# ArmazConnect_-_Rev_B3.net
KiCad netlist of a schematic drawn in EAGLE
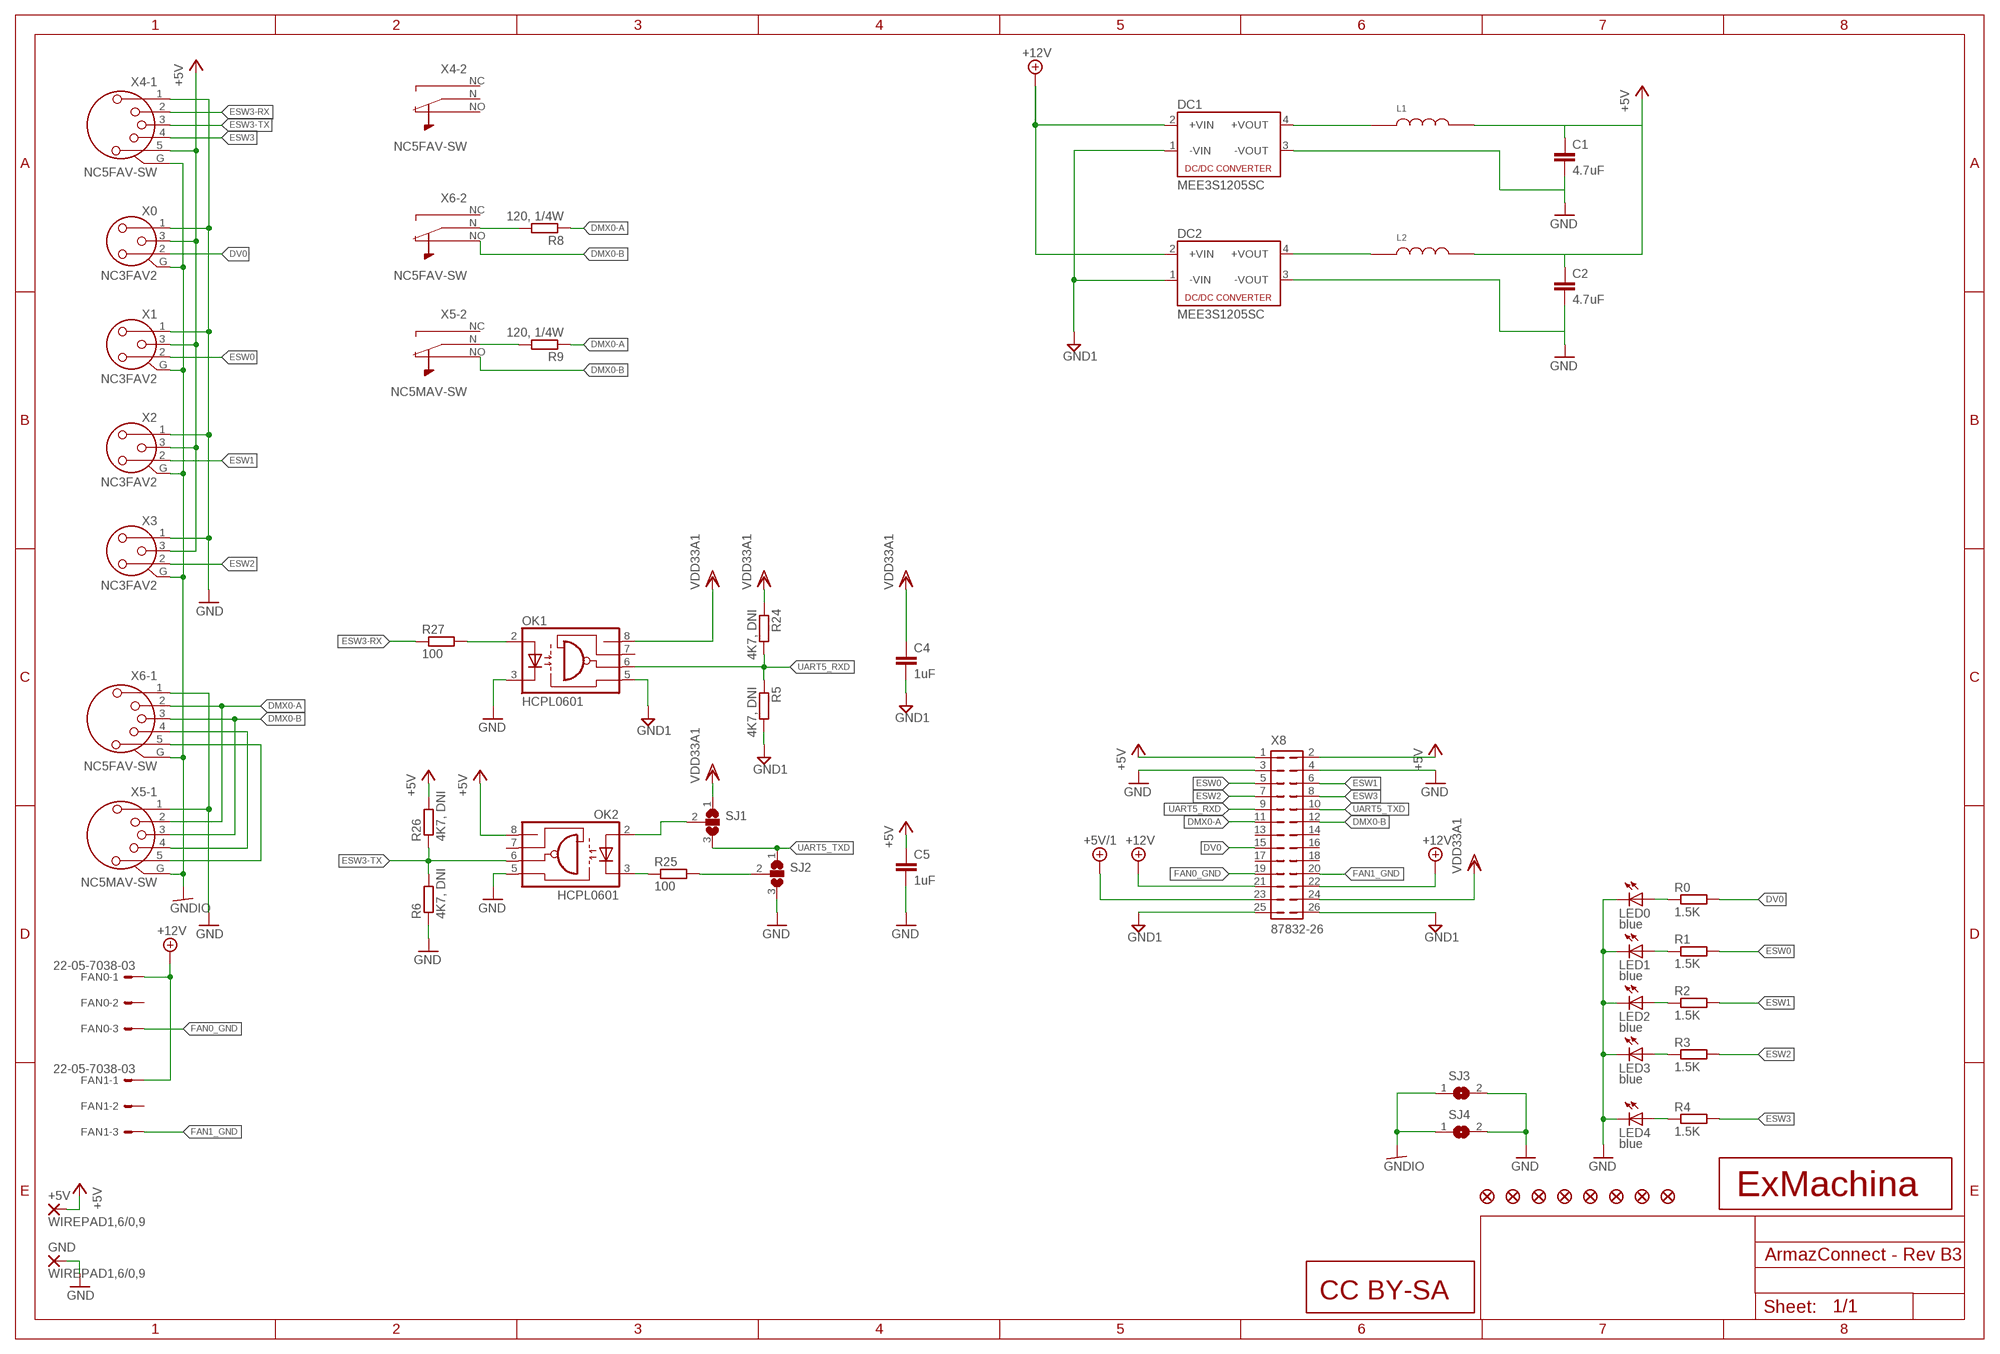
[diagram p0: schematic, sheet 1]

(export (version "E")
  (design (tool "Eeschema 10.0.6"))
  (components
    (comp (ref "+5V")
      (value "WIREPAD1,6/0,9")
      (footprint "eagle-import:1,6_0,9")
      (libsource (lib "eagle-import") (part "WIREPAD1,6/0,9"))
    )
    (comp (ref "C1")
      (value "4.7uF")
      (footprint "eagle-import:C0603")
      (fields (field (name "MF") "MULTICOMP") (field (name "MPN") "MC0603X475K6R3CT"))
      (libsource (lib "eagle-import") (part "C-EUC0603"))
    )
    (comp (ref "C2")
      (value "4.7uF")
      (footprint "eagle-import:C0603")
      (fields (field (name "MF") "MULTICOMP") (field (name "MPN") "MC0603X475K6R3CT"))
      (libsource (lib "eagle-import") (part "C-EUC0603"))
    )
    (comp (ref "C4")
      (value "1uF")
      (footprint "eagle-import:C0805")
      (fields (field (name "MF") "MULTICOMP") (field (name "MPN") "MC0805F105Z500CT"))
      (libsource (lib "eagle-import") (part "C-EUC0805"))
    )
    (comp (ref "C5")
      (value "1uF")
      (footprint "eagle-import:C0805")
      (fields (field (name "MF") "MULTICOMP") (field (name "MPN") "MC0805F105Z500CT"))
      (libsource (lib "eagle-import") (part "C-EUC0805"))
    )
    (comp (ref "DC1")
      (value "MEE3S1205SC")
      (footprint "eagle-import:MEE3")
      (fields (field (name "MF") "MURATA POWER SOLUTIONS"))
      (libsource (lib "eagle-import") (part "MEE3S1205SC"))
    )
    (comp (ref "DC2")
      (value "MEE3S1205SC")
      (footprint "eagle-import:MEE3")
      (fields (field (name "MF") "MURATA POWER SOLUTIONS"))
      (libsource (lib "eagle-import") (part "MEE3S1205SC"))
    )
    (comp (ref "FAN0")
      (value "22-05-7038-03")
      (footprint "eagle-import:7395-03")
      (fields
        (field (name "MF") "MOLEX")
        (field (name "MPN") "22-05-7038")
        (field (name "OC_FARNELL") "9731610")
      )
      (libsource (lib "eagle-import") (part "22-?-0305-7038"))
    )
    (comp (ref "FAN1")
      (value "22-05-7038-03")
      (footprint "eagle-import:7395-03")
      (fields
        (field (name "MF") "MOLEX")
        (field (name "MPN") "22-05-7038")
        (field (name "OC_FARNELL") "9731610")
      )
      (libsource (lib "eagle-import") (part "22-?-0305-7038"))
    )
    (comp (ref "FI1")
      (value "FIDUCIAL1X2")
      (footprint "eagle-import:FIDUCIAL-1X2")
      (libsource (lib "eagle-import") (part "FIDUCIAL1X2"))
    )
    (comp (ref "FI2")
      (value "FIDUCIAL1X2")
      (footprint "eagle-import:FIDUCIAL-1X2")
      (libsource (lib "eagle-import") (part "FIDUCIAL1X2"))
    )
    (comp (ref "FI3")
      (value "FIDUCIAL1X2")
      (footprint "eagle-import:FIDUCIAL-1X2")
      (libsource (lib "eagle-import") (part "FIDUCIAL1X2"))
    )
    (comp (ref "FI4")
      (value "FIDUCIAL1X2")
      (footprint "eagle-import:FIDUCIAL-1X2")
      (libsource (lib "eagle-import") (part "FIDUCIAL1X2"))
    )
    (comp (ref "FI5")
      (value "FIDUCIAL1X2")
      (footprint "eagle-import:FIDUCIAL-1X2")
      (libsource (lib "eagle-import") (part "FIDUCIAL1X2"))
    )
    (comp (ref "FI6")
      (value "FIDUCIAL1X2")
      (footprint "eagle-import:FIDUCIAL-1X2")
      (libsource (lib "eagle-import") (part "FIDUCIAL1X2"))
    )
    (comp (ref "FI7")
      (value "FIDUCIAL1X2")
      (footprint "eagle-import:FIDUCIAL-1X2")
      (libsource (lib "eagle-import") (part "FIDUCIAL1X2"))
    )
    (comp (ref "FI8")
      (value "FIDUCIAL1X2")
      (footprint "eagle-import:FIDUCIAL-1X2")
      (libsource (lib "eagle-import") (part "FIDUCIAL1X2"))
    )
    (comp (ref "GND")
      (value "WIREPAD1,6/0,9")
      (footprint "eagle-import:1,6_0,9")
      (libsource (lib "eagle-import") (part "WIREPAD1,6/0,9"))
    )
    (comp (ref "L1")
      (value "84103C")
      (footprint "eagle-import:8200")
      (fields (field (name "MF") "WURTH ELEKTRONIK") (field (name "MPN") "744045100"))
      (libsource (lib "eagle-import") (part "84103C"))
    )
    (comp (ref "L2")
      (value "84103C")
      (footprint "eagle-import:8200")
      (fields (field (name "MF") "WURTH ELEKTRONIK") (field (name "MPN") "744045100"))
      (libsource (lib "eagle-import") (part "84103C"))
    )
    (comp (ref "LED0")
      (value "blue")
      (footprint "eagle-import:CHIP-LED0603")
      (fields (field (name "MF") "MULTICOMP") (field (name "MPN") "OVS-0603"))
      (libsource (lib "eagle-import") (part "LEDCHIP-LED0603"))
    )
    (comp (ref "LED1")
      (value "blue")
      (footprint "eagle-import:CHIP-LED0603")
      (fields (field (name "MF") "MULTICOMP") (field (name "MPN") "OVS-0603"))
      (libsource (lib "eagle-import") (part "LEDCHIP-LED0603"))
    )
    (comp (ref "LED2")
      (value "blue")
      (footprint "eagle-import:CHIP-LED0603")
      (fields (field (name "MF") "MULTICOMP") (field (name "MPN") "OVS-0603"))
      (libsource (lib "eagle-import") (part "LEDCHIP-LED0603"))
    )
    (comp (ref "LED3")
      (value "blue")
      (footprint "eagle-import:CHIP-LED0603")
      (fields (field (name "MF") "MULTICOMP") (field (name "MPN") "OVS-0603"))
      (libsource (lib "eagle-import") (part "LEDCHIP-LED0603"))
    )
    (comp (ref "LED4")
      (value "blue")
      (footprint "eagle-import:CHIP-LED0603")
      (fields (field (name "MF") "MULTICOMP") (field (name "MPN") "OVS-0603"))
      (libsource (lib "eagle-import") (part "LEDCHIP-LED0603"))
    )
    (comp (ref "OK1")
      (value "HCPL0601")
      (footprint "eagle-import:SOIC08")
      (fields
        (field (name "MF") "AGILENT TECHNOLOGIES")
        (field (name "MPN") "HCPL-0601-000E")
        (field (name "MF_1") "AVAGO TECHNOLOGIES")
      )
      (libsource (lib "eagle-import") (part "HCPL0601"))
    )
    (comp (ref "OK2")
      (value "HCPL0601")
      (footprint "eagle-import:SOIC08")
      (fields
        (field (name "MF") "AGILENT TECHNOLOGIES")
        (field (name "MPN") "HCPL-0601-000E")
        (field (name "MF_1") "AVAGO TECHNOLOGIES")
      )
      (libsource (lib "eagle-import") (part "HCPL0601"))
    )
    (comp (ref "R0")
      (value "1.5K")
      (footprint "eagle-import:R0603")
      (fields (field (name "MF") "MULTICOMP") (field (name "MPN") "MCMR06X1501FTL"))
      (libsource (lib "eagle-import") (part "R-EU_R0603"))
    )
    (comp (ref "R1")
      (value "1.5K")
      (footprint "eagle-import:R0603")
      (fields (field (name "MF") "MULTICOMP") (field (name "MPN") "MCMR06X1501FTL"))
      (libsource (lib "eagle-import") (part "R-EU_R0603"))
    )
    (comp (ref "R2")
      (value "1.5K")
      (footprint "eagle-import:R0603")
      (fields (field (name "MF") "MULTICOMP") (field (name "MPN") "MCMR06X1501FTL"))
      (libsource (lib "eagle-import") (part "R-EU_R0603"))
    )
    (comp (ref "R3")
      (value "1.5K")
      (footprint "eagle-import:R0603")
      (fields (field (name "MF") "MULTICOMP") (field (name "MPN") "MCMR06X1501FTL"))
      (libsource (lib "eagle-import") (part "R-EU_R0603"))
    )
    (comp (ref "R4")
      (value "1.5K")
      (footprint "eagle-import:R0603")
      (fields (field (name "MF") "MULTICOMP") (field (name "MPN") "MCMR06X1501FTL"))
      (libsource (lib "eagle-import") (part "R-EU_R0603"))
    )
    (comp (ref "R5")
      (value "4K7, DNI")
      (footprint "eagle-import:R0603")
      (fields (field (name "MF") "MULTICOMP") (field (name "MPN") "MCMR04X3301FTL"))
      (libsource (lib "eagle-import") (part "R-EU_R0603"))
    )
    (comp (ref "R6")
      (value "4K7, DNI")
      (footprint "eagle-import:R0603")
      (fields (field (name "MF") "MULTICOMP") (field (name "MPN") "MCMR06X4701FTL"))
      (libsource (lib "eagle-import") (part "R-EU_R0603"))
    )
    (comp (ref "R8")
      (value "120, 1/4W")
      (footprint "eagle-import:R0603")
      (fields (field (name "MF") "MULTICOMP") (field (name "MPN") "MCMR06X1200FTL"))
      (libsource (lib "eagle-import") (part "R-EU_R0603"))
    )
    (comp (ref "R9")
      (value "120, 1/4W")
      (footprint "eagle-import:R0603")
      (fields (field (name "MF") "MULTICOMP") (field (name "MPN") "MCMR06X1200FTL"))
      (libsource (lib "eagle-import") (part "R-EU_R0603"))
    )
    (comp (ref "R24")
      (value "4K7, DNI")
      (footprint "eagle-import:R0603")
      (fields (field (name "MF") "MULTICOMP") (field (name "MPN") "MCMR04X3301FTL"))
      (libsource (lib "eagle-import") (part "R-EU_R0603"))
    )
    (comp (ref "R25")
      (value "100")
      (footprint "eagle-import:R0603")
      (fields (field (name "MF") "MULTICOMP") (field (name "MPN") "MCMR06X3300FTL"))
      (libsource (lib "eagle-import") (part "R-EU_R0603"))
    )
    (comp (ref "R26")
      (value "4K7, DNI")
      (footprint "eagle-import:R0603")
      (fields (field (name "MF") "MULTICOMP") (field (name "MPN") "MCMR06X4701FTL"))
      (libsource (lib "eagle-import") (part "R-EU_R0603"))
    )
    (comp (ref "R27")
      (value "100")
      (footprint "eagle-import:R0603")
      (fields (field (name "MF") "MULTICOMP") (field (name "MPN") "MCMR06X4701FTL"))
      (libsource (lib "eagle-import") (part "R-EU_R0603"))
    )
    (comp (ref "SJ1")
      (value "SJ2W")
      (footprint "eagle-import:SJ_2")
      (libsource (lib "eagle-import") (part "SJ2W"))
    )
    (comp (ref "SJ2")
      (value "SJ2W")
      (footprint "eagle-import:SJ_2")
      (libsource (lib "eagle-import") (part "SJ2W"))
    )
    (comp (ref "SJ3") (value "SJ") (footprint "eagle-import:SJ") (libsource (lib "eagle-import") (part "SJ")))
    (comp (ref "SJ4") (value "SJ") (footprint "eagle-import:SJ") (libsource (lib "eagle-import") (part "SJ")))
    (comp (ref "U$1")
      (value "EXMACHINA-LOGO-NAME")
      (footprint "eagle-import:EXM-LOGO-BASELINE")
      (libsource (lib "eagle-import") (part "EXMACHINA-LOGO-NAME"))
    )
    (comp (ref "U$2")
      (value "CC-BY-SA")
      (footprint "eagle-import:CC-BY-SA")
      (libsource (lib "eagle-import") (part "CC-BY-SA"))
    )
    (comp (ref "X0")
      (value "NC3FAV2")
      (footprint "eagle-import:NC3FAV2")
      (fields
        (field (name "MF") "NEUTRIK")
        (field (name "MPN") "NC3FAAV2")
        (field (name "OC_FARNELL") "1310038")
      )
      (libsource (lib "eagle-import") (part "NC3FAV2"))
    )
    (comp (ref "X1")
      (value "NC3FAV2")
      (footprint "eagle-import:NC3FAV2")
      (fields
        (field (name "MF") "NEUTRIK")
        (field (name "MPN") "NC3FAAV2")
        (field (name "OC_FARNELL") "1310038")
      )
      (libsource (lib "eagle-import") (part "NC3FAV2"))
    )
    (comp (ref "X2")
      (value "NC3FAV2")
      (footprint "eagle-import:NC3FAV2")
      (fields
        (field (name "MF") "NEUTRIK")
        (field (name "MPN") "NC3FAAV2")
        (field (name "OC_FARNELL") "1310038")
      )
      (libsource (lib "eagle-import") (part "NC3FAV2"))
    )
    (comp (ref "X3")
      (value "NC3FAV2")
      (footprint "eagle-import:NC3FAV2")
      (fields
        (field (name "MF") "NEUTRIK")
        (field (name "MPN") "NC3FAAV2")
        (field (name "OC_FARNELL") "1310038")
      )
      (libsource (lib "eagle-import") (part "NC3FAV2"))
    )
    (comp (ref "X4")
      (value "NC5FAV-SW")
      (footprint "eagle-import:NC5FAV-SW")
      (fields (field (name "MF") "NEUTRIK") (field (name "OC_FARNELL") "1310093"))
      (libsource (lib "eagle-import") (part "NC5?-SWFAV"))
    )
    (comp (ref "X5")
      (value "NC5MAV-SW")
      (footprint "eagle-import:NC5MAV-SW")
      (fields
        (field (name "MF") "NETRIK")
        (field (name "MF_1") "NEUTRIK")
        (field (name "OC_FARNELL") "1310098")
      )
      (libsource (lib "eagle-import") (part "NC5?-SWMAV"))
    )
    (comp (ref "X6")
      (value "NC5FAV-SW")
      (footprint "eagle-import:NC5FAV-SW")
      (fields (field (name "MF") "NEUTRIK") (field (name "OC_FARNELL") "1310093"))
      (libsource (lib "eagle-import") (part "NC5?-SWFAV"))
    )
    (comp (ref "X8")
      (value "87832-26")
      (footprint "eagle-import:87832-26")
      (fields
        (field (name "MF") "MOLEX")
        (field (name "MPN") "87832-2620")
        (field (name "OC_FARNELL") "2313712")
      )
      (libsource (lib "eagle-import") (part "87832-26"))
    )
  )
  (nets
    (net (code "1") (name "+5V") (class "Default")
      (node (ref "+5V") (pin "1") (pinfunction "P_1") (pintype "passive"))
      (node (ref "C1") (pin "1") (pinfunction "1_1") (pintype "passive"))
      (node (ref "C2") (pin "1") (pinfunction "1_1") (pintype "passive"))
      (node (ref "C5") (pin "1") (pinfunction "1_1") (pintype "passive"))
      (node (ref "L1") (pin "2") (pinfunction "2_2") (pintype "passive"))
      (node (ref "L2") (pin "2") (pinfunction "2_2") (pintype "passive"))
      (node (ref "OK2") (pin "8") (pinfunction "VCC_8") (pintype "passive"))
      (node (ref "R26") (pin "2") (pinfunction "2_2") (pintype "passive"))
      (node (ref "X0") (pin "3") (pinfunction "3_3") (pintype "passive"))
      (node (ref "X1") (pin "3") (pinfunction "3_3") (pintype "passive"))
      (node (ref "X2") (pin "3") (pinfunction "3_3") (pintype "passive"))
      (node (ref "X3") (pin "3") (pinfunction "3_3") (pintype "passive"))
      (node (ref "X4") (pin "5") (pinfunction "5_5") (pintype "passive"))
      (node (ref "X8") (pin "1") (pinfunction "1_1") (pintype "passive"))
      (node (ref "X8") (pin "2") (pinfunction "2_2") (pintype "passive"))
    )
    (net (code "2") (name "+5V{slash}1") (class "Default")
      (node (ref "X8") (pin "23") (pinfunction "23_23") (pintype "passive"))
    )
    (net (code "3") (name "+12V") (class "Default")
      (node (ref "DC1") (pin "2") (pinfunction "+VIN_2") (pintype "passive"))
      (node (ref "DC2") (pin "2") (pinfunction "+VIN_2") (pintype "passive"))
      (node (ref "FAN0") (pin "1") (pinfunction "S_1") (pintype "passive"))
      (node (ref "FAN1") (pin "1") (pinfunction "S_1") (pintype "passive"))
      (node (ref "X8") (pin "21") (pinfunction "21_21") (pintype "passive"))
      (node (ref "X8") (pin "22") (pinfunction "22_22") (pintype "passive"))
    )
    (net (code "4") (name "DMX0-A") (class "Default")
      (node (ref "R8") (pin "1") (pinfunction "1_1") (pintype "passive"))
      (node (ref "R9") (pin "1") (pinfunction "1_1") (pintype "passive"))
      (node (ref "X5") (pin "2") (pinfunction "2_2") (pintype "passive"))
      (node (ref "X6") (pin "2") (pinfunction "2_2") (pintype "passive"))
      (node (ref "X8") (pin "11") (pinfunction "11_11") (pintype "passive"))
    )
    (net (code "5") (name "DMX0-B") (class "Default")
      (node (ref "X5") (pin "3") (pinfunction "3_3") (pintype "passive"))
      (node (ref "X5") (pin "NO") (pinfunction "NO_NO") (pintype "passive"))
      (node (ref "X6") (pin "3") (pinfunction "3_3") (pintype "passive"))
      (node (ref "X6") (pin "NO") (pinfunction "NO_NO") (pintype "passive"))
      (node (ref "X8") (pin "12") (pinfunction "12_12") (pintype "passive"))
    )
    (net (code "6") (name "DV0") (class "Default")
      (node (ref "R0") (pin "2") (pinfunction "2_2") (pintype "passive"))
      (node (ref "X0") (pin "2") (pinfunction "2_2") (pintype "passive"))
      (node (ref "X8") (pin "15") (pinfunction "15_15") (pintype "passive"))
    )
    (net (code "7") (name "ESW0") (class "Default")
      (node (ref "R1") (pin "2") (pinfunction "2_2") (pintype "passive"))
      (node (ref "X1") (pin "2") (pinfunction "2_2") (pintype "passive"))
      (node (ref "X8") (pin "5") (pinfunction "5_5") (pintype "passive"))
    )
    (net (code "8") (name "ESW1") (class "Default")
      (node (ref "R2") (pin "2") (pinfunction "2_2") (pintype "passive"))
      (node (ref "X2") (pin "2") (pinfunction "2_2") (pintype "passive"))
      (node (ref "X8") (pin "6") (pinfunction "6_6") (pintype "passive"))
    )
    (net (code "9") (name "ESW2") (class "Default")
      (node (ref "R3") (pin "2") (pinfunction "2_2") (pintype "passive"))
      (node (ref "X3") (pin "2") (pinfunction "2_2") (pintype "passive"))
      (node (ref "X8") (pin "7") (pinfunction "7_7") (pintype "passive"))
    )
    (net (code "10") (name "ESW3") (class "Default")
      (node (ref "R4") (pin "2") (pinfunction "2_2") (pintype "passive"))
      (node (ref "X4") (pin "4") (pinfunction "4_4") (pintype "passive"))
      (node (ref "X8") (pin "8") (pinfunction "8_8") (pintype "passive"))
    )
    (net (code "11") (name "ESW3-RX") (class "Default")
      (node (ref "R27") (pin "1") (pinfunction "1_1") (pintype "passive"))
      (node (ref "X4") (pin "2") (pinfunction "2_2") (pintype "passive"))
    )
    (net (code "12") (name "ESW3-TX") (class "Default")
      (node (ref "OK2") (pin "6") (pinfunction "VO_6") (pintype "passive"))
      (node (ref "R26") (pin "1") (pinfunction "1_1") (pintype "passive"))
      (node (ref "R6") (pin "2") (pinfunction "2_2") (pintype "passive"))
      (node (ref "X4") (pin "3") (pinfunction "3_3") (pintype "passive"))
    )
    (net (code "13") (name "FAN0_GND") (class "Default")
      (node (ref "FAN0") (pin "3") (pinfunction "S_3") (pintype "passive"))
      (node (ref "X8") (pin "19") (pinfunction "19_19") (pintype "passive"))
    )
    (net (code "14") (name "FAN1_GND") (class "Default")
      (node (ref "FAN1") (pin "3") (pinfunction "S_3") (pintype "passive"))
      (node (ref "X8") (pin "20") (pinfunction "20_20") (pintype "passive"))
    )
    (net (code "15") (name "GND") (class "Default")
      (node (ref "C1") (pin "2") (pinfunction "2_2") (pintype "passive"))
      (node (ref "C2") (pin "2") (pinfunction "2_2") (pintype "passive"))
      (node (ref "C5") (pin "2") (pinfunction "2_2") (pintype "passive"))
      (node (ref "DC1") (pin "3") (pinfunction "-VOUT_3") (pintype "passive"))
      (node (ref "DC2") (pin "3") (pinfunction "-VOUT_3") (pintype "passive"))
      (node (ref "GND") (pin "1") (pinfunction "P_1") (pintype "passive"))
      (node (ref "LED0") (pin "C") (pinfunction "C_C") (pintype "passive"))
      (node (ref "LED1") (pin "C") (pinfunction "C_C") (pintype "passive"))
      (node (ref "LED2") (pin "C") (pinfunction "C_C") (pintype "passive"))
      (node (ref "LED3") (pin "C") (pinfunction "C_C") (pintype "passive"))
      (node (ref "LED4") (pin "C") (pinfunction "C_C") (pintype "passive"))
      (node (ref "OK1") (pin "3") (pinfunction "C_3") (pintype "passive"))
      (node (ref "OK2") (pin "5") (pinfunction "GND_5") (pintype "passive"))
      (node (ref "R6") (pin "1") (pinfunction "1_1") (pintype "passive"))
      (node (ref "SJ2") (pin "3") (pinfunction "3_3") (pintype "passive"))
      (node (ref "SJ3") (pin "2") (pinfunction "2_2") (pintype "passive"))
      (node (ref "SJ4") (pin "2") (pinfunction "2_2") (pintype "passive"))
      (node (ref "X0") (pin "1") (pinfunction "1_1") (pintype "passive"))
      (node (ref "X1") (pin "1") (pinfunction "1_1") (pintype "passive"))
      (node (ref "X2") (pin "1") (pinfunction "1_1") (pintype "passive"))
      (node (ref "X3") (pin "1") (pinfunction "1_1") (pintype "passive"))
      (node (ref "X4") (pin "1") (pinfunction "1_1") (pintype "passive"))
      (node (ref "X5") (pin "1") (pinfunction "1_1") (pintype "passive"))
      (node (ref "X6") (pin "1") (pinfunction "1_1") (pintype "passive"))
      (node (ref "X8") (pin "3") (pinfunction "3_3") (pintype "passive"))
      (node (ref "X8") (pin "4") (pinfunction "4_4") (pintype "passive"))
    )
    (net (code "16") (name "GND1") (class "Default")
      (node (ref "C4") (pin "2") (pinfunction "2_2") (pintype "passive"))
      (node (ref "DC1") (pin "1") (pinfunction "-VIN_1") (pintype "passive"))
      (node (ref "DC2") (pin "1") (pinfunction "-VIN_1") (pintype "passive"))
      (node (ref "OK1") (pin "5") (pinfunction "GND_5") (pintype "passive"))
      (node (ref "R5") (pin "2") (pinfunction "2_2") (pintype "passive"))
      (node (ref "X8") (pin "25") (pinfunction "25_25") (pintype "passive"))
      (node (ref "X8") (pin "26") (pinfunction "26_26") (pintype "passive"))
    )
    (net (code "17") (name "GNDIO") (class "Default")
      (node (ref "SJ3") (pin "1") (pinfunction "1_1") (pintype "passive"))
      (node (ref "SJ4") (pin "1") (pinfunction "1_1") (pintype "passive"))
      (node (ref "X0") (pin "G") (pinfunction "G_G") (pintype "passive"))
      (node (ref "X1") (pin "G") (pinfunction "G_G") (pintype "passive"))
      (node (ref "X2") (pin "G") (pinfunction "G_G") (pintype "passive"))
      (node (ref "X3") (pin "G") (pinfunction "G_G") (pintype "passive"))
      (node (ref "X4") (pin "G") (pinfunction "G_G") (pintype "passive"))
      (node (ref "X5") (pin "G") (pinfunction "G_G") (pintype "passive"))
      (node (ref "X6") (pin "G") (pinfunction "G_G") (pintype "passive"))
    )
    (net (code "18") (name "Net-(DC1-+VOUT)") (class "Default")
      (node (ref "DC1") (pin "4") (pinfunction "+VOUT_4") (pintype "passive"))
      (node (ref "L1") (pin "1") (pinfunction "1_1") (pintype "passive"))
    )
    (net (code "19") (name "Net-(DC2-+VOUT)") (class "Default")
      (node (ref "DC2") (pin "4") (pinfunction "+VOUT_4") (pintype "passive"))
      (node (ref "L2") (pin "1") (pinfunction "1_1") (pintype "passive"))
    )
    (net (code "20") (name "Net-(LED0-PadA)") (class "Default")
      (node (ref "LED0") (pin "A") (pinfunction "A_A") (pintype "passive"))
      (node (ref "R0") (pin "1") (pinfunction "1_1") (pintype "passive"))
    )
    (net (code "21") (name "Net-(LED1-PadA)") (class "Default")
      (node (ref "LED1") (pin "A") (pinfunction "A_A") (pintype "passive"))
      (node (ref "R1") (pin "1") (pinfunction "1_1") (pintype "passive"))
    )
    (net (code "22") (name "Net-(LED2-PadA)") (class "Default")
      (node (ref "LED2") (pin "A") (pinfunction "A_A") (pintype "passive"))
      (node (ref "R2") (pin "1") (pinfunction "1_1") (pintype "passive"))
    )
    (net (code "23") (name "Net-(LED3-PadA)") (class "Default")
      (node (ref "LED3") (pin "A") (pinfunction "A_A") (pintype "passive"))
      (node (ref "R3") (pin "1") (pinfunction "1_1") (pintype "passive"))
    )
    (net (code "24") (name "Net-(LED4-PadA)") (class "Default")
      (node (ref "LED4") (pin "A") (pinfunction "A_A") (pintype "passive"))
      (node (ref "R4") (pin "1") (pinfunction "1_1") (pintype "passive"))
    )
    (net (code "25") (name "Net-(OK1-A)") (class "Default")
      (node (ref "OK1") (pin "2") (pinfunction "A_2") (pintype "passive"))
      (node (ref "R27") (pin "2") (pinfunction "2_2") (pintype "passive"))
    )
    (net (code "26") (name "Net-(OK2-A)") (class "Default")
      (node (ref "OK2") (pin "2") (pinfunction "A_2") (pintype "passive"))
      (node (ref "SJ1") (pin "2") (pinfunction "2_2") (pintype "passive"))
    )
    (net (code "27") (name "Net-(OK2-C)") (class "Default")
      (node (ref "OK2") (pin "3") (pinfunction "C_3") (pintype "passive"))
      (node (ref "R25") (pin "1") (pinfunction "1_1") (pintype "passive"))
    )
    (net (code "28") (name "Net-(R8-Pad2)") (class "Default")
      (node (ref "R8") (pin "2") (pinfunction "2_2") (pintype "passive"))
      (node (ref "X6") (pin "N") (pinfunction "N_N") (pintype "passive"))
    )
    (net (code "29") (name "Net-(R9-Pad2)") (class "Default")
      (node (ref "R9") (pin "2") (pinfunction "2_2") (pintype "passive"))
      (node (ref "X5") (pin "N") (pinfunction "N_N") (pintype "passive"))
    )
    (net (code "30") (name "Net-(R25-Pad2)") (class "Default")
      (node (ref "R25") (pin "2") (pinfunction "2_2") (pintype "passive"))
      (node (ref "SJ2") (pin "2") (pinfunction "2_2") (pintype "passive"))
    )
    (net (code "31") (name "Net-(X5-Pad4)") (class "Default")
      (node (ref "X5") (pin "4") (pinfunction "4_4") (pintype "passive"))
      (node (ref "X6") (pin "4") (pinfunction "4_4") (pintype "passive"))
    )
    (net (code "32") (name "Net-(X5-Pad5)") (class "Default")
      (node (ref "X5") (pin "5") (pinfunction "5_5") (pintype "passive"))
      (node (ref "X6") (pin "5") (pinfunction "5_5") (pintype "passive"))
    )
    (net (code "33") (name "UART5_RXD") (class "Default")
      (node (ref "OK1") (pin "6") (pinfunction "VO_6") (pintype "passive"))
      (node (ref "R24") (pin "2") (pinfunction "2_2") (pintype "passive"))
      (node (ref "R5") (pin "1") (pinfunction "1_1") (pintype "passive"))
      (node (ref "X8") (pin "9") (pinfunction "9_9") (pintype "passive"))
    )
    (net (code "34") (name "UART5_TXD") (class "Default")
      (node (ref "SJ1") (pin "3") (pinfunction "3_3") (pintype "passive"))
      (node (ref "SJ2") (pin "1") (pinfunction "1_1") (pintype "passive"))
      (node (ref "X8") (pin "10") (pinfunction "10_10") (pintype "passive"))
    )
    (net (code "35") (name "VDD33A1") (class "Default")
      (node (ref "C4") (pin "1") (pinfunction "1_1") (pintype "passive"))
      (node (ref "OK1") (pin "8") (pinfunction "VCC_8") (pintype "passive"))
      (node (ref "R24") (pin "1") (pinfunction "1_1") (pintype "passive"))
      (node (ref "SJ1") (pin "1") (pinfunction "1_1") (pintype "passive"))
      (node (ref "X8") (pin "24") (pinfunction "24_24") (pintype "passive"))
    )
    (net (code "36") (name "unconnected-(FAN0B-S-Pad2)") (class "Default")
      (node (ref "FAN0") (pin "2") (pinfunction "S_2") (pintype "passive"))
    )
    (net (code "37") (name "unconnected-(FAN1B-S-Pad2)") (class "Default")
      (node (ref "FAN1") (pin "2") (pinfunction "S_2") (pintype "passive"))
    )
    (net (code "38") (name "unconnected-(OK1-VE-Pad7)") (class "Default")
      (node (ref "OK1") (pin "7") (pinfunction "VE_7") (pintype "passive"))
    )
    (net (code "39") (name "unconnected-(OK2-VE-Pad7)") (class "Default")
      (node (ref "OK2") (pin "7") (pinfunction "VE_7") (pintype "passive"))
    )
    (net (code "40") (name "unconnected-(X4-PadN)") (class "Default")
      (node (ref "X4") (pin "N") (pinfunction "N_N") (pintype "passive"))
    )
    (net (code "41") (name "unconnected-(X4-PadNC)") (class "Default")
      (node (ref "X4") (pin "NC") (pinfunction "NC_NC") (pintype "passive"))
    )
    (net (code "42") (name "unconnected-(X4-PadNO)") (class "Default")
      (node (ref "X4") (pin "NO") (pinfunction "NO_NO") (pintype "passive"))
    )
    (net (code "43") (name "unconnected-(X5-PadNC)") (class "Default")
      (node (ref "X5") (pin "NC") (pinfunction "NC_NC") (pintype "passive"))
    )
    (net (code "44") (name "unconnected-(X6-PadNC)") (class "Default")
      (node (ref "X6") (pin "NC") (pinfunction "NC_NC") (pintype "passive"))
    )
    (net (code "45") (name "unconnected-(X8-Pad13)") (class "Default")
      (node (ref "X8") (pin "13") (pinfunction "13_13") (pintype "passive"))
    )
    (net (code "46") (name "unconnected-(X8-Pad14)") (class "Default")
      (node (ref "X8") (pin "14") (pinfunction "14_14") (pintype "passive"))
    )
    (net (code "47") (name "unconnected-(X8-Pad16)") (class "Default")
      (node (ref "X8") (pin "16") (pinfunction "16_16") (pintype "passive"))
    )
    (net (code "48") (name "unconnected-(X8-Pad17)") (class "Default")
      (node (ref "X8") (pin "17") (pinfunction "17_17") (pintype "passive"))
    )
    (net (code "49") (name "unconnected-(X8-Pad18)") (class "Default")
      (node (ref "X8") (pin "18") (pinfunction "18_18") (pintype "passive"))
    )
  )
)
